# VideoOut.net
KiCad netlist of a schematic drawn in EAGLE
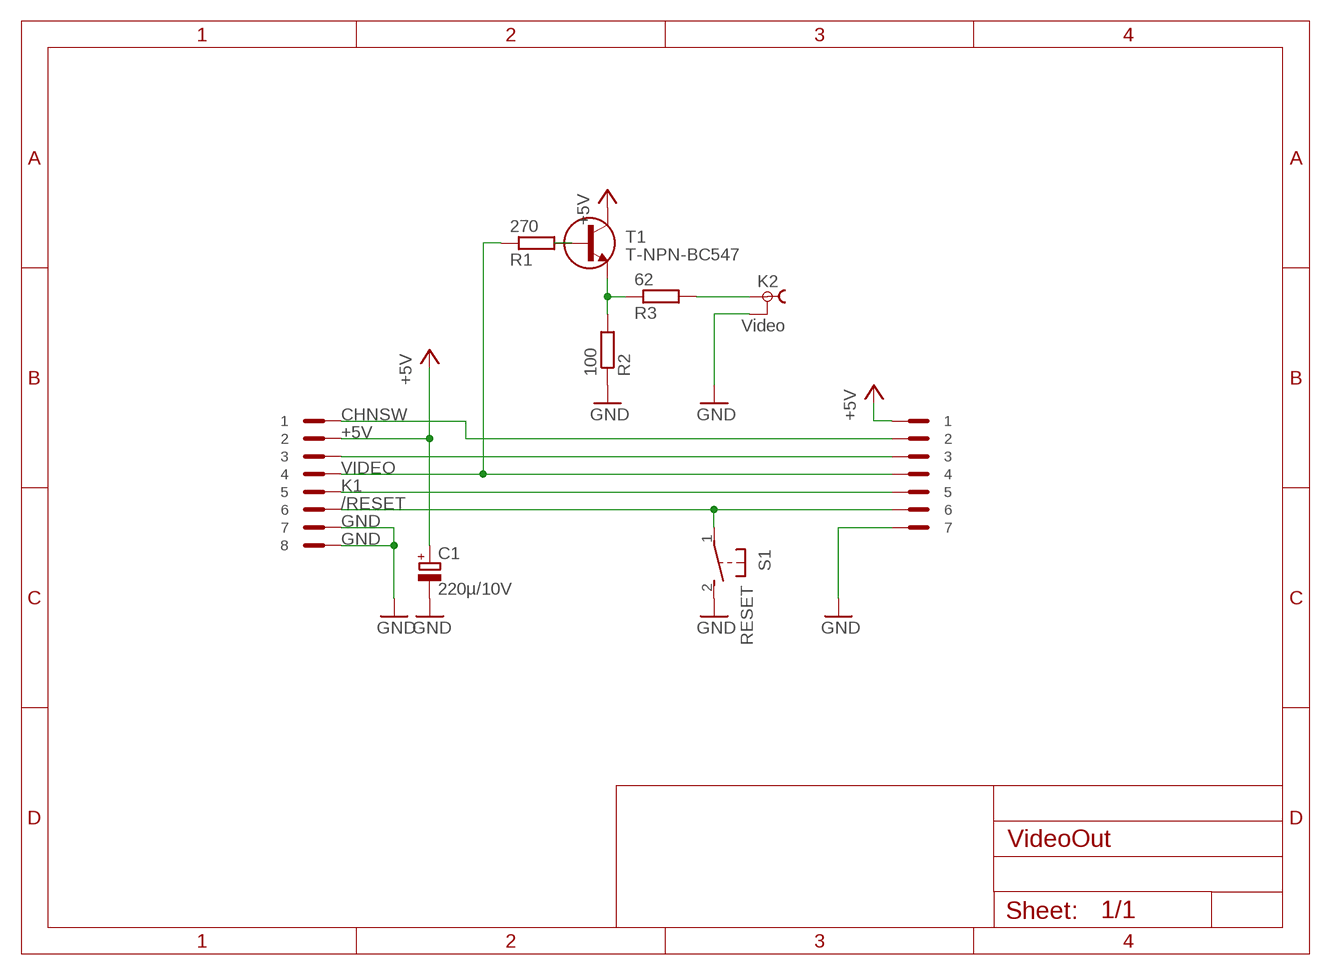
[diagram p0: schematic, sheet 1]

(export (version "E")
  (design (tool "Eeschema 10.0.6"))
  (components
    (comp (ref "C1")
      (value "220µ/10V")
      (footprint "eagle-import:E2,5-6")
      (libsource (lib "eagle-import") (part "CPOL-EUE2.5-6"))
    )
    (comp (ref "K2")
      (value "Video")
      (footprint "eagle-import:TOBU3")
      (fields (field (name "MF") "FARNELL") (field (name "MPN") "TOBU 3"))
      (libsource (lib "eagle-import") (part "TOBU3"))
    )
    (comp (ref "K3")
      (value "PINHEAD-1X7")
      (footprint "eagle-import:PINHEAD1X7")
      (libsource (lib "eagle-import") (part "PINHEAD-1X7"))
    )
    (comp (ref "K6")
      (value "PINHEAD-2X4")
      (footprint "eagle-import:PINHEAD2X4")
      (libsource (lib "eagle-import") (part "PINHEAD-2X4"))
    )
    (comp (ref "R1")
      (value "270")
      (footprint "eagle-import:R207_10")
      (libsource (lib "eagle-import") (part "RR207/10"))
    )
    (comp (ref "R2")
      (value "100")
      (footprint "eagle-import:R207_10")
      (libsource (lib "eagle-import") (part "RR207/10"))
    )
    (comp (ref "R3")
      (value "62")
      (footprint "eagle-import:R207_10")
      (libsource (lib "eagle-import") (part "RR207/10"))
    )
    (comp (ref "S1")
      (value "RESET")
      (footprint "eagle-import:B3F-31XX")
      (fields (field (name "MPN") "B3F-3100"))
      (libsource (lib "eagle-import") (part "31-XX"))
    )
    (comp (ref "T1")
      (value "T-NPN-BC547")
      (footprint "eagle-import:TO92")
      (libsource (lib "eagle-import") (part "T-NPN-BC547"))
    )
  )
  (nets
    (net (code "1") (name "+5V") (class "Default")
      (node (ref "C1") (pin "+") (pinfunction "+_+") (pintype "passive"))
      (node (ref "K3") (pin "1") (pinfunction "1_1") (pintype "bidirectional"))
      (node (ref "K6") (pin "2") (pinfunction "2_2") (pintype "bidirectional"))
      (node (ref "T1") (pin "C") (pinfunction "C_C") (pintype "passive"))
    )
    (net (code "2") (name "/CHNSW") (class "Default")
      (node (ref "K3") (pin "2") (pinfunction "2_2") (pintype "bidirectional"))
      (node (ref "K6") (pin "1") (pinfunction "1_1") (pintype "bidirectional"))
    )
    (net (code "3") (name "/K1") (class "Default")
      (node (ref "K3") (pin "5") (pinfunction "5_5") (pintype "bidirectional"))
      (node (ref "K6") (pin "5") (pinfunction "5_5") (pintype "bidirectional"))
    )
    (net (code "4") (name "/VIDEO") (class "Default")
      (node (ref "K3") (pin "4") (pinfunction "4_4") (pintype "bidirectional"))
      (node (ref "K6") (pin "4") (pinfunction "4_4") (pintype "bidirectional"))
      (node (ref "R1") (pin "1") (pinfunction "1_1") (pintype "passive"))
    )
    (net (code "5") (name "/{slash}RESET") (class "Default")
      (node (ref "K3") (pin "6") (pinfunction "6_6") (pintype "bidirectional"))
      (node (ref "K6") (pin "6") (pinfunction "6_6") (pintype "bidirectional"))
      (node (ref "S1") (pin "1") (pinfunction "P_1") (pintype "passive"))
    )
    (net (code "6") (name "GND") (class "Default")
      (node (ref "C1") (pin "-") (pinfunction "-_-") (pintype "passive"))
      (node (ref "K2") (pin "2") (pinfunction "2_2") (pintype "passive"))
      (node (ref "K2") (pin "2@1") (pinfunction "2_2@1") (pintype "passive"))
      (node (ref "K2") (pin "2@2") (pinfunction "2_2@2") (pintype "passive"))
      (node (ref "K3") (pin "7") (pinfunction "7_7") (pintype "bidirectional"))
      (node (ref "K6") (pin "7") (pinfunction "7_7") (pintype "bidirectional"))
      (node (ref "K6") (pin "8") (pinfunction "8_8") (pintype "bidirectional"))
      (node (ref "R2") (pin "1") (pinfunction "1_1") (pintype "passive"))
      (node (ref "S1") (pin "2") (pinfunction "S_2") (pintype "passive"))
    )
    (net (code "7") (name "Net-(K2-Pad1)") (class "Default")
      (node (ref "K2") (pin "1") (pinfunction "1_1") (pintype "passive"))
      (node (ref "R3") (pin "2") (pinfunction "2_2") (pintype "passive"))
    )
    (net (code "8") (name "Net-(K3-Pad3)") (class "Default")
      (node (ref "K3") (pin "3") (pinfunction "3_3") (pintype "bidirectional"))
      (node (ref "K6") (pin "3") (pinfunction "3_3") (pintype "bidirectional"))
    )
    (net (code "9") (name "Net-(R1-Pad2)") (class "Default")
      (node (ref "R1") (pin "2") (pinfunction "2_2") (pintype "passive"))
      (node (ref "T1") (pin "B") (pinfunction "B_B") (pintype "passive"))
    )
    (net (code "10") (name "Net-(R2-Pad2)") (class "Default")
      (node (ref "R2") (pin "2") (pinfunction "2_2") (pintype "passive"))
      (node (ref "R3") (pin "1") (pinfunction "1_1") (pintype "passive"))
      (node (ref "T1") (pin "E") (pinfunction "E_E") (pintype "passive"))
    )
  )
)
